# ft231x-breakout-v11-openSX70version-5P-S.net
KiCad netlist of a schematic drawn in EAGLE
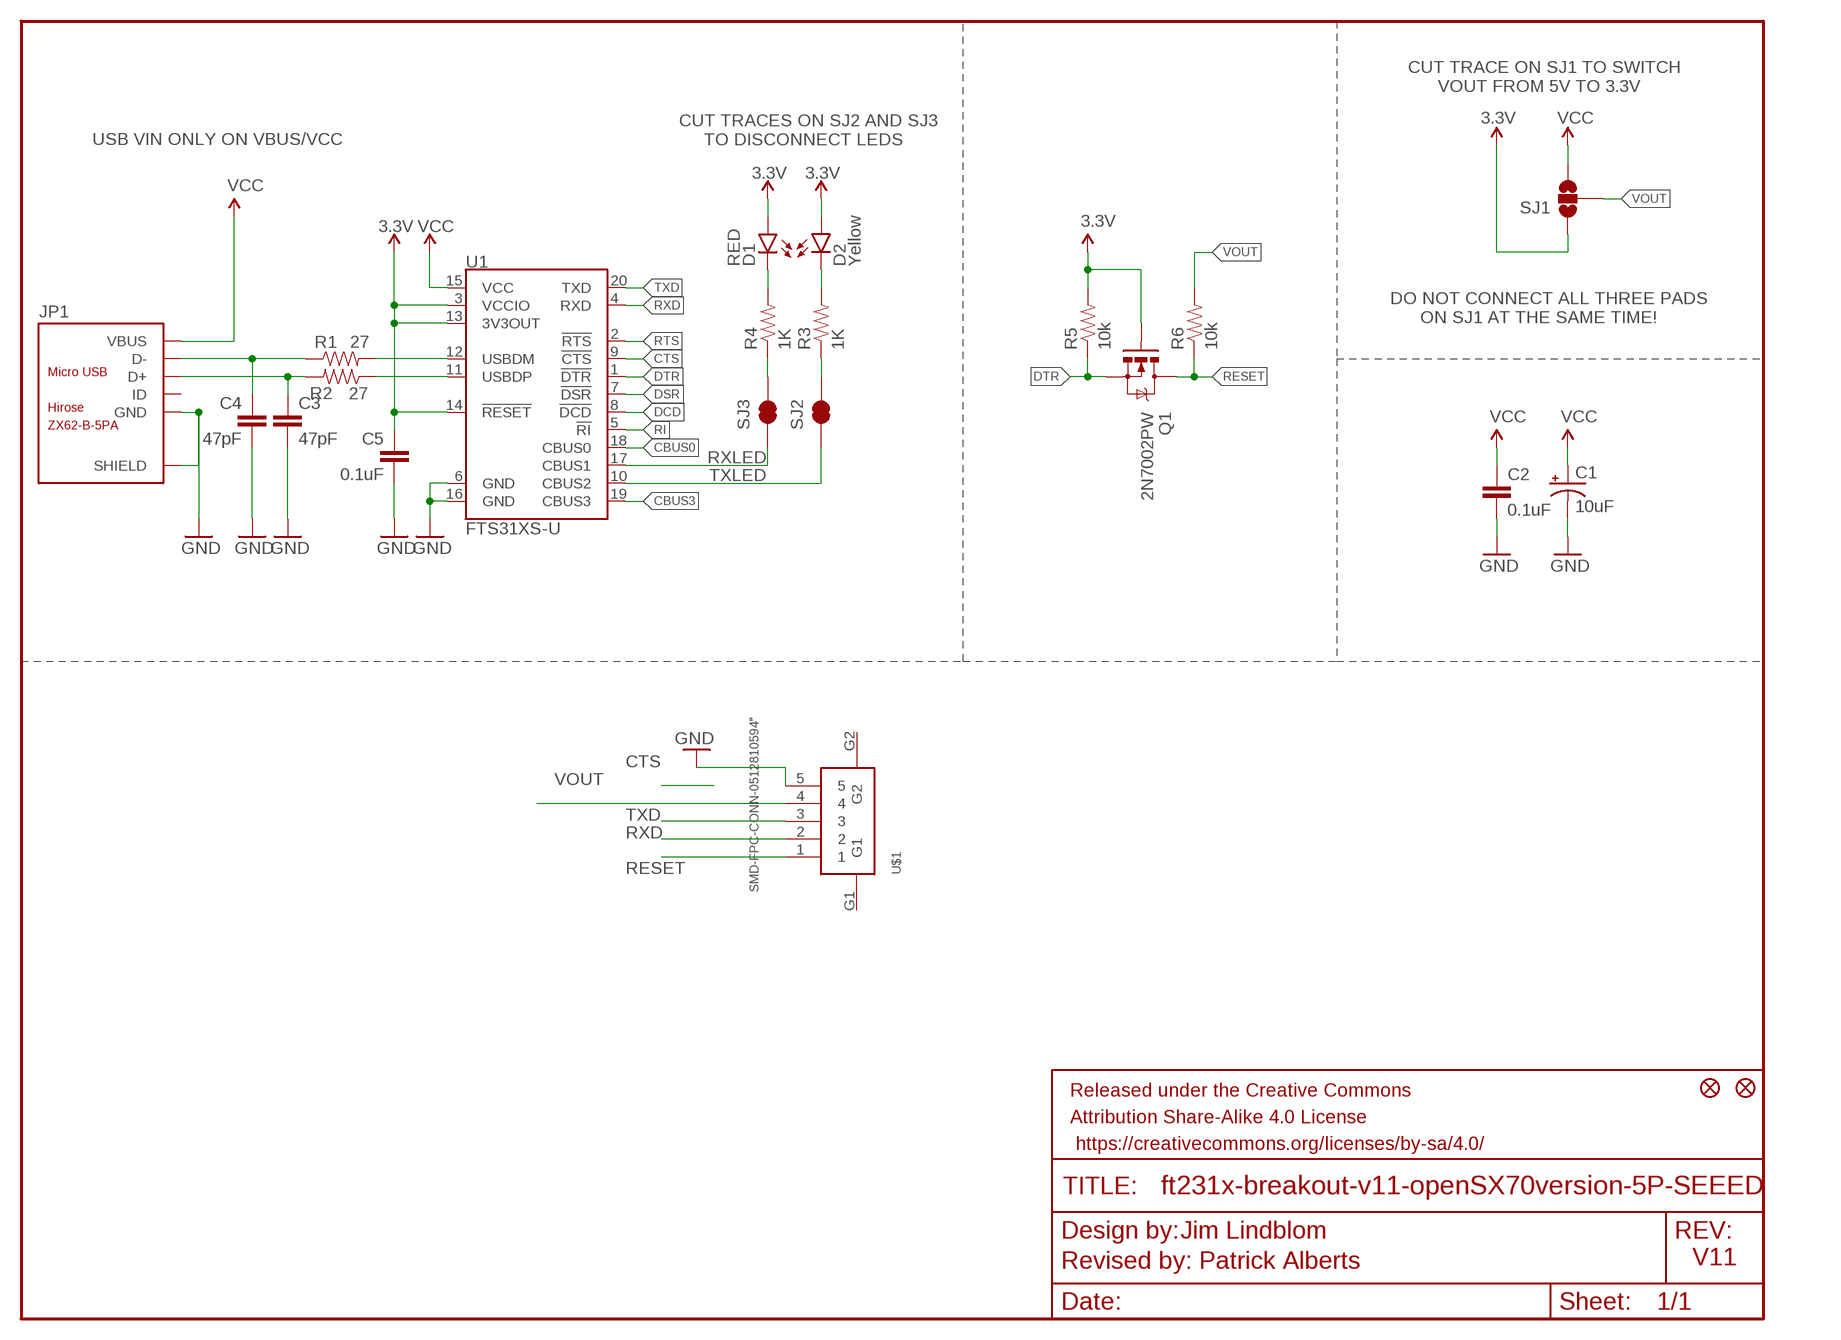
[diagram p0: schematic, sheet 1]

(export (version "E")
  (design (tool "Eeschema 10.0.6"))
  (components
    (comp (ref "C1")
      (value "10uF")
      (footprint "eagle-import:EIA3216")
      (libsource (lib "eagle-import") (part "10UF-16V-10%(TANT)"))
    )
    (comp (ref "C2")
      (value "0.1uF")
      (footprint "eagle-import:0603-CAP")
      (libsource (lib "eagle-import") (part "0.1UF-25V(+80/-20%)(0603)"))
    )
    (comp (ref "C3")
      (value "47pF")
      (footprint "eagle-import:0603-CAP")
      (libsource (lib "eagle-import") (part "47PF-50V-5%(0603)"))
    )
    (comp (ref "C4")
      (value "47pF")
      (footprint "eagle-import:0603-CAP")
      (libsource (lib "eagle-import") (part "47PF-50V-5%(0603)"))
    )
    (comp (ref "C5")
      (value "0.1uF")
      (footprint "eagle-import:0603-CAP")
      (libsource (lib "eagle-import") (part "0.1UF-25V(+80/-20%)(0603)"))
    )
    (comp (ref "D1")
      (value "RED")
      (footprint "eagle-import:LED-0603")
      (libsource (lib "eagle-import") (part "LED-RED0603"))
    )
    (comp (ref "D2")
      (value "Yellow")
      (footprint "eagle-import:LED-0603")
      (libsource (lib "eagle-import") (part "LED-YELLOW0603"))
    )
    (comp (ref "FRAME1")
      (value "FRAME-LETTER")
      (footprint "eagle-import:CREATIVE_COMMONS")
      (libsource (lib "eagle-import") (part "FRAME-LETTER"))
    )
    (comp (ref "JP1")
      (value "ZX62-B-5PA")
      (footprint "eagle-import:MICRO-USB5+6P-SMD-0.65-AB")
      (libsource (lib "eagle-import") (part "MICRO-USB-SMD(ZX62-B-5PA)"))
    )
    (comp (ref "JP5")
      (value "FIDUCIAL1X2")
      (footprint "eagle-import:FIDUCIAL-1X2")
      (libsource (lib "eagle-import") (part "FIDUCIAL1X2"))
    )
    (comp (ref "JP6")
      (value "FIDUCIAL1X2")
      (footprint "eagle-import:FIDUCIAL-1X2")
      (libsource (lib "eagle-import") (part "FIDUCIAL1X2"))
    )
    (comp (ref "Q1")
      (value "2N7002PW")
      (footprint "eagle-import:SOT323")
      (libsource (lib "eagle-import") (part "MOSFET-NCHANNEL2N7002PW"))
    )
    (comp (ref "R1")
      (value "27")
      (footprint "eagle-import:0603-RES")
      (libsource (lib "eagle-import") (part "27OHM1/10W1%(0603)0603-RES"))
    )
    (comp (ref "R2")
      (value "27")
      (footprint "eagle-import:0603-RES")
      (libsource (lib "eagle-import") (part "27OHM1/10W1%(0603)0603-RES"))
    )
    (comp (ref "R3")
      (value "1K")
      (footprint "eagle-import:0603-RES")
      (libsource (lib "eagle-import") (part "1KOHM-1/10W-1%(0603)"))
    )
    (comp (ref "R4")
      (value "1K")
      (footprint "eagle-import:0603-RES")
      (libsource (lib "eagle-import") (part "1KOHM-1/10W-1%(0603)"))
    )
    (comp (ref "R5")
      (value "10k")
      (footprint "eagle-import:0603-RES@1")
      (libsource (lib "eagle-import") (part "10KOHM1/10W1%(0603)0603"))
    )
    (comp (ref "R6")
      (value "10k")
      (footprint "eagle-import:0603-RES@1")
      (libsource (lib "eagle-import") (part "10KOHM1/10W1%(0603)0603"))
    )
    (comp (ref "SJ1")
      (value "SOLDERJUMPER_2WAYS")
      (footprint "eagle-import:SJ_3")
      (libsource (lib "eagle-import") (part "SOLDERJUMPER_2WAYS"))
    )
    (comp (ref "SJ2")
      (value "TXLED")
      (footprint "eagle-import:SJ_2S-TRACE")
      (libsource (lib "eagle-import") (part "SOLDERJUMPERTRACE"))
    )
    (comp (ref "SJ3")
      (value "RXLED")
      (footprint "eagle-import:PAD-JUMPER-2-NC_BY_TRACE_YES_SILK")
      (libsource (lib "eagle-import") (part "JUMPER-PAD-2-NC_BY_TRACE"))
    )
    (comp (ref "U$1")
      (value "SMD-FPC-CONN-0512810594\"")
      (footprint "eagle-import:51281-0594")
      (libsource (lib "eagle-import") (part "SMD-FPC-CONN-0512810594{dblquote}"))
    )
    (comp (ref "U1")
      (value "FTS31XS-U")
      (footprint "eagle-import:SSOP20_L")
      (libsource (lib "eagle-import") (part "FT231XS"))
    )
  )
  (nets
    (net (code "1") (name "/RXLED") (class "Default")
      (node (ref "SJ3") (pin "1") (pinfunction "1_1") (pintype "passive"))
      (node (ref "U1") (pin "17") (pinfunction "CBUS1_17") (pintype "bidirectional"))
    )
    (net (code "2") (name "/TXLED") (class "Default")
      (node (ref "SJ2") (pin "1") (pinfunction "1_1") (pintype "passive"))
      (node (ref "U1") (pin "10") (pinfunction "CBUS2_10") (pintype "bidirectional"))
    )
    (net (code "3") (name "3.3V") (class "Default")
      (node (ref "C5") (pin "1") (pinfunction "1_1") (pintype "passive"))
      (node (ref "D1") (pin "A") (pinfunction "A_A") (pintype "passive"))
      (node (ref "D2") (pin "A") (pinfunction "A_A") (pintype "passive"))
      (node (ref "Q1") (pin "1") (pinfunction "G_1") (pintype "passive"))
      (node (ref "R5") (pin "2") (pinfunction "2_2") (pintype "passive"))
      (node (ref "SJ1") (pin "1") (pinfunction "1_1") (pintype "passive"))
      (node (ref "U1") (pin "13") (pinfunction "3V3OUT_13") (pintype "bidirectional"))
      (node (ref "U1") (pin "14") (pinfunction "~{RESET}_14") (pintype "bidirectional"))
      (node (ref "U1") (pin "3") (pinfunction "VCCIO_3") (pintype "bidirectional"))
    )
    (net (code "4") (name "CBUS0") (class "Default")
      (node (ref "U1") (pin "18") (pinfunction "CBUS0_18") (pintype "bidirectional"))
    )
    (net (code "5") (name "CBUS3") (class "Default")
      (node (ref "U1") (pin "19") (pinfunction "CBUS3_19") (pintype "bidirectional"))
    )
    (net (code "6") (name "CTS") (class "Default")
      (node (ref "U1") (pin "9") (pinfunction "~{CTS}_9") (pintype "bidirectional"))
    )
    (net (code "7") (name "DCD") (class "Default")
      (node (ref "U1") (pin "8") (pinfunction "~{DCD}_8") (pintype "bidirectional"))
    )
    (net (code "8") (name "DSR") (class "Default")
      (node (ref "U1") (pin "7") (pinfunction "~{DSR}_7") (pintype "bidirectional"))
    )
    (net (code "9") (name "DTR") (class "Default")
      (node (ref "Q1") (pin "2") (pinfunction "S_2") (pintype "passive"))
      (node (ref "R5") (pin "1") (pinfunction "1_1") (pintype "passive"))
      (node (ref "U1") (pin "1") (pinfunction "~{DTR}_1") (pintype "bidirectional"))
    )
    (net (code "10") (name "GND") (class "Default")
      (node (ref "C1") (pin "C") (pinfunction "-_C") (pintype "passive"))
      (node (ref "C2") (pin "2") (pinfunction "2_2") (pintype "passive"))
      (node (ref "C3") (pin "2") (pinfunction "2_2") (pintype "passive"))
      (node (ref "C4") (pin "2") (pinfunction "2_2") (pintype "passive"))
      (node (ref "C5") (pin "2") (pinfunction "2_2") (pintype "passive"))
      (node (ref "JP1") (pin "5") (pinfunction "GND_5") (pintype "power_in"))
      (node (ref "JP1") (pin "P1") (pinfunction "SHIELD_P1") (pintype "power_in"))
      (node (ref "JP1") (pin "P2") (pinfunction "SHIELD_P2") (pintype "power_in"))
      (node (ref "JP1") (pin "P3") (pinfunction "SHIELD_P3") (pintype "power_in"))
      (node (ref "JP1") (pin "P4") (pinfunction "SHIELD_P4") (pintype "power_in"))
      (node (ref "JP1") (pin "P5") (pinfunction "SHIELD_P5") (pintype "power_in"))
      (node (ref "JP1") (pin "P6") (pinfunction "SHIELD_P6") (pintype "power_in"))
      (node (ref "U$1") (pin "5") (pinfunction "5_5") (pintype "bidirectional"))
      (node (ref "U1") (pin "16") (pinfunction "GND_16") (pintype "bidirectional"))
      (node (ref "U1") (pin "6") (pinfunction "GND_6") (pintype "bidirectional"))
    )
    (net (code "11") (name "Net-(D1-PadC)") (class "Default")
      (node (ref "D1") (pin "C") (pinfunction "C_C") (pintype "passive"))
      (node (ref "R4") (pin "2") (pinfunction "2_2") (pintype "passive"))
    )
    (net (code "12") (name "Net-(D2-PadC)") (class "Default")
      (node (ref "D2") (pin "C") (pinfunction "C_C") (pintype "passive"))
      (node (ref "R3") (pin "2") (pinfunction "2_2") (pintype "passive"))
    )
    (net (code "13") (name "Net-(JP1-D+)") (class "Default")
      (node (ref "C3") (pin "1") (pinfunction "1_1") (pintype "passive"))
      (node (ref "JP1") (pin "3") (pinfunction "D+_3") (pintype "bidirectional"))
      (node (ref "R2") (pin "2") (pinfunction "2_2") (pintype "passive"))
    )
    (net (code "14") (name "Net-(JP1-D-)") (class "Default")
      (node (ref "C4") (pin "1") (pinfunction "1_1") (pintype "passive"))
      (node (ref "JP1") (pin "2") (pinfunction "D-_2") (pintype "bidirectional"))
      (node (ref "R1") (pin "1") (pinfunction "1_1") (pintype "passive"))
    )
    (net (code "15") (name "Net-(R3-Pad1)") (class "Default")
      (node (ref "R3") (pin "1") (pinfunction "1_1") (pintype "passive"))
      (node (ref "SJ2") (pin "2") (pinfunction "2_2") (pintype "passive"))
    )
    (net (code "16") (name "Net-(R4-Pad1)") (class "Default")
      (node (ref "R4") (pin "1") (pinfunction "1_1") (pintype "passive"))
      (node (ref "SJ3") (pin "2") (pinfunction "2_2") (pintype "passive"))
    )
    (net (code "17") (name "Net-(U1-USBDM)") (class "Default")
      (node (ref "R1") (pin "2") (pinfunction "2_2") (pintype "passive"))
      (node (ref "U1") (pin "12") (pinfunction "USBDM_12") (pintype "bidirectional"))
    )
    (net (code "18") (name "Net-(U1-USBDP)") (class "Default")
      (node (ref "R2") (pin "1") (pinfunction "1_1") (pintype "passive"))
      (node (ref "U1") (pin "11") (pinfunction "USBDP_11") (pintype "bidirectional"))
    )
    (net (code "19") (name "RESET") (class "Default")
      (node (ref "Q1") (pin "3") (pinfunction "D_3") (pintype "passive"))
      (node (ref "R6") (pin "1") (pinfunction "1_1") (pintype "passive"))
      (node (ref "U$1") (pin "1") (pinfunction "1_1") (pintype "bidirectional"))
    )
    (net (code "20") (name "RI") (class "Default")
      (node (ref "U1") (pin "5") (pinfunction "~{RI}_5") (pintype "bidirectional"))
    )
    (net (code "21") (name "RTS") (class "Default")
      (node (ref "U1") (pin "2") (pinfunction "~{RTS}_2") (pintype "bidirectional"))
    )
    (net (code "22") (name "RXD") (class "Default")
      (node (ref "U$1") (pin "2") (pinfunction "2_2") (pintype "bidirectional"))
      (node (ref "U1") (pin "4") (pinfunction "RXD_4") (pintype "bidirectional"))
    )
    (net (code "23") (name "TXD") (class "Default")
      (node (ref "U$1") (pin "3") (pinfunction "3_3") (pintype "bidirectional"))
      (node (ref "U1") (pin "20") (pinfunction "TXD_20") (pintype "bidirectional"))
    )
    (net (code "24") (name "VCC") (class "Default")
      (node (ref "C1") (pin "A") (pinfunction "+_A") (pintype "passive"))
      (node (ref "C2") (pin "1") (pinfunction "1_1") (pintype "passive"))
      (node (ref "JP1") (pin "1") (pinfunction "VBUS_1") (pintype "power_in"))
      (node (ref "SJ1") (pin "3") (pinfunction "3_3") (pintype "passive"))
      (node (ref "U1") (pin "15") (pinfunction "VCC_15") (pintype "bidirectional"))
    )
    (net (code "25") (name "VOUT") (class "Default")
      (node (ref "R6") (pin "2") (pinfunction "2_2") (pintype "passive"))
      (node (ref "SJ1") (pin "2") (pinfunction "2_2") (pintype "passive"))
      (node (ref "U$1") (pin "4") (pinfunction "4_4") (pintype "bidirectional"))
    )
    (net (code "26") (name "unconnected-(JP1-ID-Pad4)") (class "Default")
      (node (ref "JP1") (pin "4") (pinfunction "ID_4") (pintype "bidirectional"))
    )
    (net (code "27") (name "unconnected-(U$1-PadG1)") (class "Default")
      (node (ref "U$1") (pin "G1") (pinfunction "G1_G1") (pintype "bidirectional"))
    )
    (net (code "28") (name "unconnected-(U$1-PadG2)") (class "Default")
      (node (ref "U$1") (pin "G2") (pinfunction "G2_G2") (pintype "bidirectional"))
    )
  )
)
